# MCU_MKE185F512VLH16.net
KiCad netlist of a schematic drawn in Altium Designer
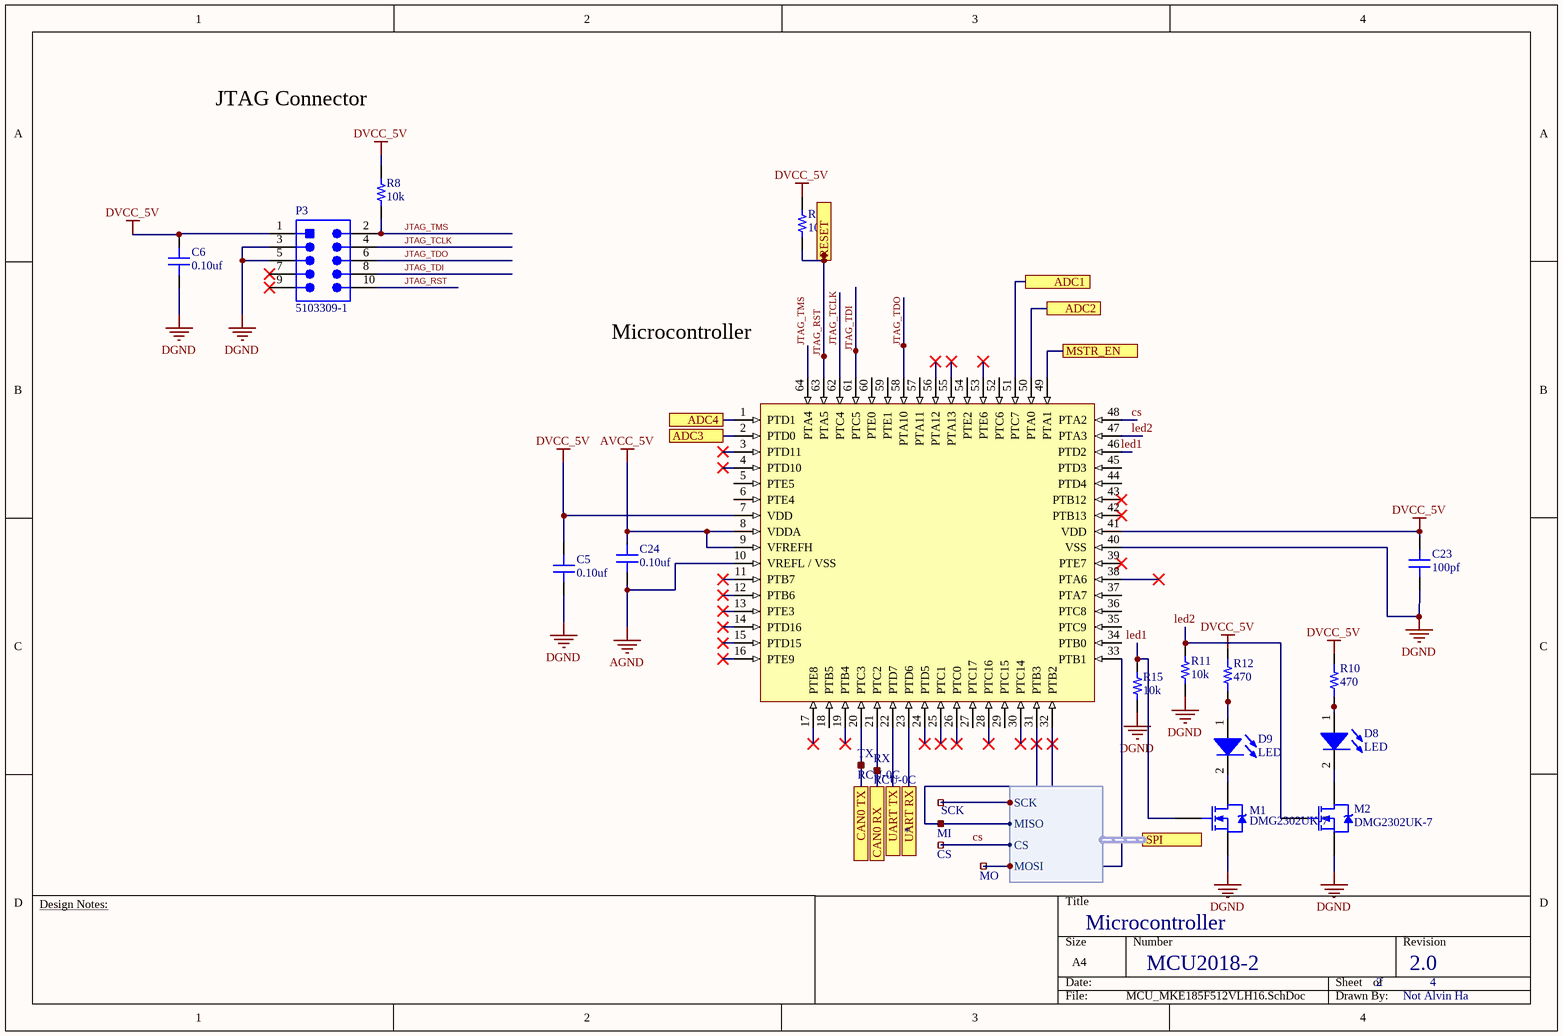
[diagram p0: MCU_MKE185F512VLH16.SchDoc]

(export (version "E")
  (design (tool "Eeschema 10.0.6"))
  (components
    (comp (ref "C5")
      (value "0.10uf")
      (footprint "CAP 0603/1608")
      (fields
        (field (name "Comment") "Capacitor MLCC 0.10uf 25V CAP 0603/1608")
        (field (name "CREATED_BY") "Nick Mah")
      )
      (libsource (lib "Altium-Lib") (part "Capacitor"))
    )
    (comp (ref "C6")
      (value "0.10uf")
      (footprint "CAP 0603/1608")
      (fields
        (field (name "Comment") "Capacitor MLCC 0.10uf 16V CAP 0603/1608")
        (field (name "CREATED_BY") "Nick Mah")
      )
      (libsource (lib "Altium-Lib") (part "Capacitor"))
    )
    (comp (ref "C23")
      (value "100pf")
      (footprint "CAP 0603/1608")
      (fields
        (field (name "Comment") "Capacitor MLCC 100pf 25V CAP 0603/1608")
        (field (name "CREATED_BY") "Nick Mah")
      )
      (libsource (lib "Altium-Lib") (part "Capacitor"))
    )
    (comp (ref "C24")
      (value "0.10uf")
      (footprint "CAP 0603/1608")
      (fields
        (field (name "Comment") "Capacitor MLCC 0.10uf 25V CAP 0603/1608")
        (field (name "CREATED_BY") "Nick Mah")
      )
      (libsource (lib "Altium-Lib") (part "Capacitor"))
    )
    (comp (ref "CS") (value "RCU-0C") (footprint "RCU-0C") (libsource (lib "Altium-Lib") (part "RCU-0C")))
    (comp (ref "D8") (value "LED") (footprint "0805_LED") (libsource (lib "Altium-Lib") (part "LED")))
    (comp (ref "D9") (value "LED") (footprint "0805_LED") (libsource (lib "Altium-Lib") (part "LED")))
    (comp (ref "M1")
      (value "DMG2302UK-7")
      (footprint "SOT23-3")
      (description "MOSFET N-CHANNEL 30V 5A SOT23")
      (fields (field (name "CREATED_BY") "Angel"))
      (libsource (lib "Altium-Lib") (part "DMG2302UK-7"))
    )
    (comp (ref "M2")
      (value "DMG2302UK-7")
      (footprint "SOT23-3")
      (description "MOSFET N-CHANNEL 30V 5A SOT23")
      (fields (field (name "CREATED_BY") "Angel"))
      (libsource (lib "Altium-Lib") (part "DMG2302UK-7"))
    )
    (comp (ref "MI") (value "RCU-0C") (footprint "RCU-0C") (libsource (lib "Altium-Lib") (part "RCU-0C")))
    (comp (ref "MO") (value "RCU-0C") (footprint "RCU-0C") (libsource (lib "Altium-Lib") (part "RCU-0C")))
    (comp (ref "P3")
      (value "5103309-1")
      (footprint "HDR2X5_SMT")
      (description "2 row connector")
      (fields (field (name "CREATED_BY") "Aiku"))
      (libsource (lib "Altium-Lib") (part "CN-2P-M-R10"))
    )
    (comp (ref "R8")
      (value "10k")
      (footprint "RES 0603/1608")
      (fields
        (field (name "TOLERANCE") "1%")
        (field (name "POWER") "1/10W")
        (field (name "Comment") "Resistor 10k 0603 1/10W 1%")
        (field (name "CREATED_BY") "Nick Mah")
      )
      (libsource (lib "") (part "Resistor_1"))
    )
    (comp (ref "R9")
      (value "10k")
      (footprint "RES 0603/1608")
      (fields
        (field (name "TOLERANCE") "5%")
        (field (name "POWER") "1/10W")
        (field (name "Comment") "Resistor 10k 0603 1/10W 5%")
        (field (name "CREATED_BY") "Nick Mah")
      )
      (libsource (lib "") (part "Resistor_1"))
    )
    (comp (ref "R10")
      (value "470")
      (footprint "RES 0603/1608")
      (fields
        (field (name "TOLERANCE") "5%")
        (field (name "POWER") "1/10W")
        (field (name "Comment") "Resistor 470 0603 1/10W 5%")
        (field (name "CREATED_BY") "Nick Mah")
      )
      (libsource (lib "Altium-Lib") (part "Resistor"))
    )
    (comp (ref "R11")
      (value "10k")
      (footprint "RES 0603/1608")
      (fields
        (field (name "TOLERANCE") "1%")
        (field (name "POWER") "1/10W")
        (field (name "Comment") "Resistor 10k 0603 1/10W 1%")
        (field (name "CREATED_BY") "Nick Mah")
      )
      (libsource (lib "") (part "Resistor_1"))
    )
    (comp (ref "R12")
      (value "470")
      (footprint "RES 0603/1608")
      (fields
        (field (name "TOLERANCE") "5%")
        (field (name "POWER") "1/10W")
        (field (name "Comment") "Resistor 470 0603 1/10W 5%")
        (field (name "CREATED_BY") "Nick Mah")
      )
      (libsource (lib "Altium-Lib") (part "Resistor"))
    )
    (comp (ref "R15")
      (value "10k")
      (footprint "RES 0603/1608")
      (fields
        (field (name "TOLERANCE") "1%")
        (field (name "POWER") "1/10W")
        (field (name "Comment") "Resistor 10k 0603 1/10W 1%")
        (field (name "CREATED_BY") "Nick Mah")
      )
      (libsource (lib "") (part "Resistor_1"))
    )
    (comp (ref "RX") (value "RCU-0C") (footprint "RCU-0C") (libsource (lib "Altium-Lib") (part "RCU-0C")))
    (comp (ref "SCK") (value "RCU-0C") (footprint "RCU-0C") (libsource (lib "Altium-Lib") (part "RCU-0C")))
    (comp (ref "TX") (value "RCU-0C") (footprint "RCU-0C") (libsource (lib "Altium-Lib") (part "RCU-0C")))
    (comp (ref "U7")
      (value "~")
      (footprint "TQFP64")
      (libsource (lib "Altium-Lib") (part "MKE18F512 VLH16 MCU"))
    )
  )
  (nets
    (net (code "2") (name "/ADC1") (class "Default")
      (node (ref "U7") (pin "51") (pinfunction "PTC7_51") (pintype "input"))
    )
    (net (code "3") (name "/ADC2") (class "Default")
      (node (ref "U7") (pin "50") (pinfunction "PTA0_50") (pintype "input"))
    )
    (net (code "4") (name "/ADC3") (class "Default")
      (node (ref "U7") (pin "2") (pinfunction "PTD0_2") (pintype "input"))
    )
    (net (code "5") (name "/ADC4") (class "Default")
      (node (ref "U7") (pin "1") (pinfunction "PTD1_1") (pintype "input"))
    )
    (net (code "6") (name "/CAN0 RX") (class "Default")
      (node (ref "RX") (pin "1") (pintype "passive"))
      (node (ref "U7") (pin "21") (pinfunction "PTC2_21") (pintype "input"))
    )
    (net (code "7") (name "/CAN0 TX") (class "Default")
      (node (ref "TX") (pin "1") (pintype "passive"))
      (node (ref "U7") (pin "20") (pinfunction "PTC3_20") (pintype "input"))
    )
    (net (code "8") (name "/JTAG_RST") (class "Default")
      (node (ref "P3") (pin "10") (pinfunction "10_10") (pintype "passive"))
      (node (ref "R9") (pin "1") (pinfunction "1_1") (pintype "passive"))
      (node (ref "U7") (pin "63") (pinfunction "PTA5_63") (pintype "input"))
    )
    (net (code "9") (name "/JTAG_TCLK") (class "Default")
      (node (ref "P3") (pin "4") (pinfunction "4_4") (pintype "passive"))
      (node (ref "U7") (pin "62") (pinfunction "PTC4_62") (pintype "input"))
    )
    (net (code "10") (name "/JTAG_TDI") (class "Default")
      (node (ref "P3") (pin "8") (pinfunction "8_8") (pintype "passive"))
      (node (ref "U7") (pin "61") (pinfunction "PTC5_61") (pintype "input"))
    )
    (net (code "11") (name "/JTAG_TDO") (class "Default")
      (node (ref "P3") (pin "6") (pinfunction "6_6") (pintype "passive"))
      (node (ref "U7") (pin "58") (pinfunction "PTA10_58") (pintype "input"))
    )
    (net (code "12") (name "/JTAG_TMS") (class "Default")
      (node (ref "P3") (pin "2") (pinfunction "2_2") (pintype "passive"))
      (node (ref "R8") (pin "1") (pinfunction "1_1") (pintype "passive"))
      (node (ref "U7") (pin "64") (pinfunction "PTA4_64") (pintype "input"))
    )
    (net (code "13") (name "/MSTR_EN") (class "Default")
      (node (ref "U7") (pin "49") (pinfunction "PTA1_49") (pintype "input"))
    )
    (net (code "14") (name "/UART RX") (class "Default")
      (node (ref "U7") (pin "23") (pinfunction "PTD6_23") (pintype "input"))
    )
    (net (code "15") (name "/UART TX") (class "Default")
      (node (ref "U7") (pin "22") (pinfunction "PTD7_22") (pintype "input"))
    )
    (net (code "16") (name "/cs") (class "Default")
      (node (ref "CS") (pin "1") (pintype "passive"))
      (node (ref "U7") (pin "48") (pinfunction "PTA2_48") (pintype "input"))
    )
    (net (code "17") (name "/led1") (class "Default")
      (node (ref "M1") (pin "1") (pinfunction "G_1") (pintype "passive"))
      (node (ref "R15") (pin "2") (pinfunction "2_2") (pintype "passive"))
      (node (ref "U7") (pin "46") (pinfunction "PTD2_46") (pintype "input"))
    )
    (net (code "18") (name "/led2") (class "Default")
      (node (ref "M2") (pin "1") (pinfunction "G_1") (pintype "passive"))
      (node (ref "R11") (pin "2") (pinfunction "2_2") (pintype "passive"))
      (node (ref "U7") (pin "47") (pinfunction "PTA3_47") (pintype "input"))
    )
    (net (code "20") (name "AGND") (class "Default")
      (node (ref "C24") (pin "1") (pinfunction "1_1") (pintype "passive"))
      (node (ref "U7") (pin "10") (pinfunction "VREFL_/_VSS_10") (pintype "input"))
    )
    (net (code "21") (name "AVCC_5V") (class "Default")
      (node (ref "C24") (pin "2") (pinfunction "2_2") (pintype "passive"))
      (node (ref "U7") (pin "8") (pinfunction "VDDA_8") (pintype "input"))
      (node (ref "U7") (pin "9") (pinfunction "VFREFH_9") (pintype "input"))
    )
    (net (code "22") (name "DGND") (class "Default")
      (node (ref "C23") (pin "1") (pinfunction "1_1") (pintype "passive"))
      (node (ref "C5") (pin "1") (pinfunction "1_1") (pintype "passive"))
      (node (ref "C6") (pin "1") (pinfunction "1_1") (pintype "passive"))
      (node (ref "M1") (pin "2") (pinfunction "S_2") (pintype "passive"))
      (node (ref "M2") (pin "2") (pinfunction "S_2") (pintype "passive"))
      (node (ref "P3") (pin "3") (pinfunction "3_3") (pintype "passive"))
      (node (ref "P3") (pin "5") (pinfunction "5_5") (pintype "passive"))
      (node (ref "R11") (pin "1") (pinfunction "1_1") (pintype "passive"))
      (node (ref "R15") (pin "1") (pinfunction "1_1") (pintype "passive"))
      (node (ref "U7") (pin "40") (pinfunction "VSS_40") (pintype "input"))
    )
    (net (code "23") (name "DVCC_5V") (class "Default")
      (node (ref "C23") (pin "2") (pinfunction "2_2") (pintype "passive"))
      (node (ref "C5") (pin "2") (pinfunction "2_2") (pintype "passive"))
      (node (ref "C6") (pin "2") (pinfunction "2_2") (pintype "passive"))
      (node (ref "P3") (pin "1") (pinfunction "1_1") (pintype "passive"))
      (node (ref "R10") (pin "2") (pinfunction "2_2") (pintype "passive"))
      (node (ref "R12") (pin "2") (pinfunction "2_2") (pintype "passive"))
      (node (ref "R8") (pin "2") (pinfunction "2_2") (pintype "passive"))
      (node (ref "R9") (pin "2") (pinfunction "2_2") (pintype "passive"))
      (node (ref "U7") (pin "41") (pinfunction "VDD_41") (pintype "input"))
      (node (ref "U7") (pin "7") (pinfunction "VDD_7") (pintype "input"))
    )
    (net (code "24") (name "Net-(D8-A)") (class "Default")
      (node (ref "D8") (pin "1") (pinfunction "A_1") (pintype "passive"))
      (node (ref "R10") (pin "1") (pinfunction "1_1") (pintype "passive"))
    )
    (net (code "25") (name "Net-(D8-K)") (class "Default")
      (node (ref "D8") (pin "2") (pinfunction "K_2") (pintype "passive"))
      (node (ref "M2") (pin "3") (pinfunction "D_3") (pintype "passive"))
    )
    (net (code "26") (name "Net-(D9-A)") (class "Default")
      (node (ref "D9") (pin "1") (pinfunction "A_1") (pintype "passive"))
      (node (ref "R12") (pin "1") (pinfunction "1_1") (pintype "passive"))
    )
    (net (code "27") (name "Net-(D9-K)") (class "Default")
      (node (ref "D9") (pin "2") (pinfunction "K_2") (pintype "passive"))
      (node (ref "M1") (pin "3") (pinfunction "D_3") (pintype "passive"))
    )
    (net (code "28") (name "Net-(U7-PTB1)") (class "Default")
      (node (ref "MO") (pin "1") (pintype "passive"))
      (node (ref "U7") (pin "33") (pinfunction "PTB1_33") (pintype "input"))
    )
    (net (code "29") (name "Net-(U7-PTB2)") (class "Default")
      (node (ref "SCK") (pin "1") (pintype "passive"))
      (node (ref "U7") (pin "32") (pinfunction "PTB2_32") (pintype "input"))
    )
    (net (code "30") (name "Net-(U7-PTB3)") (class "Default")
      (node (ref "MI") (pin "1") (pintype "passive"))
      (node (ref "U7") (pin "31") (pinfunction "PTB3_31") (pintype "input"))
    )
    (net (code "31") (name "unconnected-(P3-Pad7)") (class "Default")
      (node (ref "P3") (pin "7") (pinfunction "7_7") (pintype "passive+no_connect"))
    )
    (net (code "32") (name "unconnected-(P3-Pad9)") (class "Default")
      (node (ref "P3") (pin "9") (pinfunction "9_9") (pintype "passive+no_connect"))
    )
    (net (code "33") (name "unconnected-(U7-PTA6-Pad38)") (class "Default")
      (node (ref "U7") (pin "38") (pinfunction "PTA6_38") (pintype "input+no_connect"))
    )
    (net (code "34") (name "unconnected-(U7-PTA7-Pad37)") (class "Default")
      (node (ref "U7") (pin "37") (pinfunction "PTA7_37") (pintype "input"))
    )
    (net (code "35") (name "unconnected-(U7-PTA11-Pad57)") (class "Default")
      (node (ref "U7") (pin "57") (pinfunction "PTA11_57") (pintype "input"))
    )
    (net (code "36") (name "unconnected-(U7-PTA12-Pad56)") (class "Default")
      (node (ref "U7") (pin "56") (pinfunction "PTA12_56") (pintype "input+no_connect"))
    )
    (net (code "37") (name "unconnected-(U7-PTA13-Pad55)") (class "Default")
      (node (ref "U7") (pin "55") (pinfunction "PTA13_55") (pintype "input+no_connect"))
    )
    (net (code "38") (name "unconnected-(U7-PTB0-Pad34)") (class "Default")
      (node (ref "U7") (pin "34") (pinfunction "PTB0_34") (pintype "input"))
    )
    (net (code "39") (name "unconnected-(U7-PTB4-Pad19)") (class "Default")
      (node (ref "U7") (pin "19") (pinfunction "PTB4_19") (pintype "input+no_connect"))
    )
    (net (code "40") (name "unconnected-(U7-PTB5-Pad18)") (class "Default")
      (node (ref "U7") (pin "18") (pinfunction "PTB5_18") (pintype "input"))
    )
    (net (code "41") (name "unconnected-(U7-PTB6-Pad12)") (class "Default")
      (node (ref "U7") (pin "12") (pinfunction "PTB6_12") (pintype "input+no_connect"))
    )
    (net (code "42") (name "unconnected-(U7-PTB7-Pad11)") (class "Default")
      (node (ref "U7") (pin "11") (pinfunction "PTB7_11") (pintype "input+no_connect"))
    )
    (net (code "43") (name "unconnected-(U7-PTB12-Pad43)") (class "Default")
      (node (ref "U7") (pin "43") (pinfunction "PTB12_43") (pintype "input+no_connect"))
    )
    (net (code "44") (name "unconnected-(U7-PTB13-Pad42)") (class "Default")
      (node (ref "U7") (pin "42") (pinfunction "PTB13_42") (pintype "input+no_connect"))
    )
    (net (code "45") (name "unconnected-(U7-PTC0-Pad26)") (class "Default")
      (node (ref "U7") (pin "26") (pinfunction "PTC0_26") (pintype "input+no_connect"))
    )
    (net (code "46") (name "unconnected-(U7-PTC1-Pad25)") (class "Default")
      (node (ref "U7") (pin "25") (pinfunction "PTC1_25") (pintype "input+no_connect"))
    )
    (net (code "47") (name "unconnected-(U7-PTC6-Pad52)") (class "Default")
      (node (ref "U7") (pin "52") (pinfunction "PTC6_52") (pintype "input"))
    )
    (net (code "48") (name "unconnected-(U7-PTC8-Pad36)") (class "Default")
      (node (ref "U7") (pin "36") (pinfunction "PTC8_36") (pintype "input"))
    )
    (net (code "49") (name "unconnected-(U7-PTC9-Pad35)") (class "Default")
      (node (ref "U7") (pin "35") (pinfunction "PTC9_35") (pintype "input"))
    )
    (net (code "50") (name "unconnected-(U7-PTC14-Pad30)") (class "Default")
      (node (ref "U7") (pin "30") (pinfunction "PTC14_30") (pintype "input+no_connect"))
    )
    (net (code "51") (name "unconnected-(U7-PTC15-Pad29)") (class "Default")
      (node (ref "U7") (pin "29") (pinfunction "PTC15_29") (pintype "input"))
    )
    (net (code "52") (name "unconnected-(U7-PTC16-Pad28)") (class "Default")
      (node (ref "U7") (pin "28") (pinfunction "PTC16_28") (pintype "input+no_connect"))
    )
    (net (code "53") (name "unconnected-(U7-PTC17-Pad27)") (class "Default")
      (node (ref "U7") (pin "27") (pinfunction "PTC17_27") (pintype "input"))
    )
    (net (code "54") (name "unconnected-(U7-PTD3-Pad45)") (class "Default")
      (node (ref "U7") (pin "45") (pinfunction "PTD3_45") (pintype "input"))
    )
    (net (code "55") (name "unconnected-(U7-PTD4-Pad44)") (class "Default")
      (node (ref "U7") (pin "44") (pinfunction "PTD4_44") (pintype "input"))
    )
    (net (code "56") (name "unconnected-(U7-PTD5-Pad24)") (class "Default")
      (node (ref "U7") (pin "24") (pinfunction "PTD5_24") (pintype "input+no_connect"))
    )
    (net (code "57") (name "unconnected-(U7-PTD10-Pad4)") (class "Default")
      (node (ref "U7") (pin "4") (pinfunction "PTD10_4") (pintype "input+no_connect"))
    )
    (net (code "58") (name "unconnected-(U7-PTD11-Pad3)") (class "Default")
      (node (ref "U7") (pin "3") (pinfunction "PTD11_3") (pintype "input+no_connect"))
    )
    (net (code "59") (name "unconnected-(U7-PTD15-Pad15)") (class "Default")
      (node (ref "U7") (pin "15") (pinfunction "PTD15_15") (pintype "input+no_connect"))
    )
    (net (code "60") (name "unconnected-(U7-PTD16-Pad14)") (class "Default")
      (node (ref "U7") (pin "14") (pinfunction "PTD16_14") (pintype "input+no_connect"))
    )
    (net (code "61") (name "unconnected-(U7-PTE0-Pad60)") (class "Default")
      (node (ref "U7") (pin "60") (pinfunction "PTE0_60") (pintype "input"))
    )
    (net (code "62") (name "unconnected-(U7-PTE1-Pad59)") (class "Default")
      (node (ref "U7") (pin "59") (pinfunction "PTE1_59") (pintype "input"))
    )
    (net (code "63") (name "unconnected-(U7-PTE2-Pad54)") (class "Default")
      (node (ref "U7") (pin "54") (pinfunction "PTE2_54") (pintype "input"))
    )
    (net (code "64") (name "unconnected-(U7-PTE3-Pad13)") (class "Default")
      (node (ref "U7") (pin "13") (pinfunction "PTE3_13") (pintype "input+no_connect"))
    )
    (net (code "65") (name "unconnected-(U7-PTE4-Pad6)") (class "Default")
      (node (ref "U7") (pin "6") (pinfunction "PTE4_6") (pintype "input"))
    )
    (net (code "66") (name "unconnected-(U7-PTE5-Pad5)") (class "Default")
      (node (ref "U7") (pin "5") (pinfunction "PTE5_5") (pintype "input"))
    )
    (net (code "67") (name "unconnected-(U7-PTE6-Pad53)") (class "Default")
      (node (ref "U7") (pin "53") (pinfunction "PTE6_53") (pintype "input+no_connect"))
    )
    (net (code "68") (name "unconnected-(U7-PTE7-Pad39)") (class "Default")
      (node (ref "U7") (pin "39") (pinfunction "PTE7_39") (pintype "input+no_connect"))
    )
    (net (code "69") (name "unconnected-(U7-PTE8-Pad17)") (class "Default")
      (node (ref "U7") (pin "17") (pinfunction "PTE8_17") (pintype "input+no_connect"))
    )
    (net (code "70") (name "unconnected-(U7-PTE9-Pad16)") (class "Default")
      (node (ref "U7") (pin "16") (pinfunction "PTE9_16") (pintype "input+no_connect"))
    )
  )
)
